# 1A18J3_1A19J1_A.net
KiCad netlist of a schematic drawn in Altium Designer
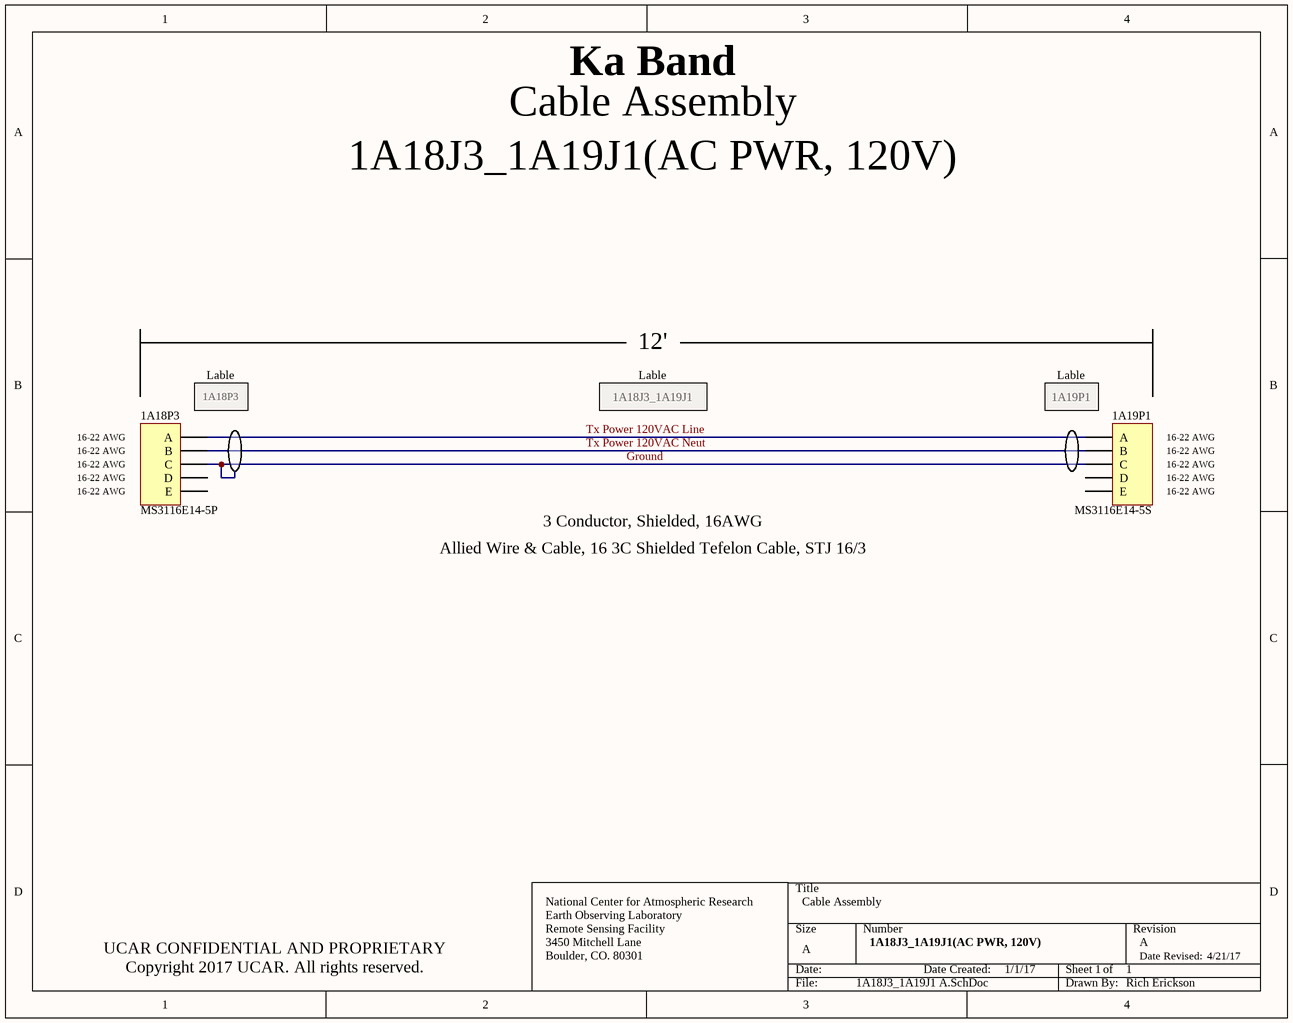
[diagram p0: 1A18J3_1A19J1 A.SchDoc]

(export (version "E")
  (design (tool "Eeschema 10.0.6"))
  (components
    (comp (ref "1A18P3")
      (value "MS3116E14-5P")
      (footprint "HDR1X5")
      (description "Header, 5-Pin")
      (fields (field (name "PUBLISHER") "Altium Limited"))
      (libsource (lib "") (part "Header 5_1"))
    )
    (comp (ref "1A19P1")
      (value "MS3116E14-5S")
      (footprint "HDR1X5")
      (description "Header, 5-Pin")
      (fields (field (name "PUBLISHER") "Altium Limited"))
      (libsource (lib "Miscellaneous Connectors") (part "Header 5"))
    )
  )
  (nets
    (net (code "1") (name "/Ground") (class "Default")
      (node (ref "1A18P3") (pin "3") (pinfunction "C_3") (pintype "passive"))
      (node (ref "1A19P1") (pin "3") (pinfunction "C_3") (pintype "passive"))
    )
    (net (code "2") (name "/Tx Power 120VAC Line") (class "Default")
      (node (ref "1A18P3") (pin "1") (pinfunction "A_1") (pintype "passive"))
      (node (ref "1A19P1") (pin "1") (pinfunction "A_1") (pintype "passive"))
    )
    (net (code "3") (name "/Tx Power 120VAC Neut") (class "Default")
      (node (ref "1A18P3") (pin "2") (pinfunction "B_2") (pintype "passive"))
      (node (ref "1A19P1") (pin "2") (pinfunction "B_2") (pintype "passive"))
    )
    (net (code "4") (name "unconnected-(1A18P3-D-Pad4)") (class "Default")
      (node (ref "1A18P3") (pin "4") (pinfunction "D_4") (pintype "passive"))
    )
    (net (code "5") (name "unconnected-(1A18P3-E-Pad5)") (class "Default")
      (node (ref "1A18P3") (pin "5") (pinfunction "E_5") (pintype "passive"))
    )
    (net (code "6") (name "unconnected-(1A19P1-D-Pad4)") (class "Default")
      (node (ref "1A19P1") (pin "4") (pinfunction "D_4") (pintype "passive"))
    )
    (net (code "7") (name "unconnected-(1A19P1-E-Pad5)") (class "Default")
      (node (ref "1A19P1") (pin "5") (pinfunction "E_5") (pintype "passive"))
    )
  )
)
